# WiFi_Relays_Board_Kit.net
KiCad netlist of a schematic drawn in EAGLE
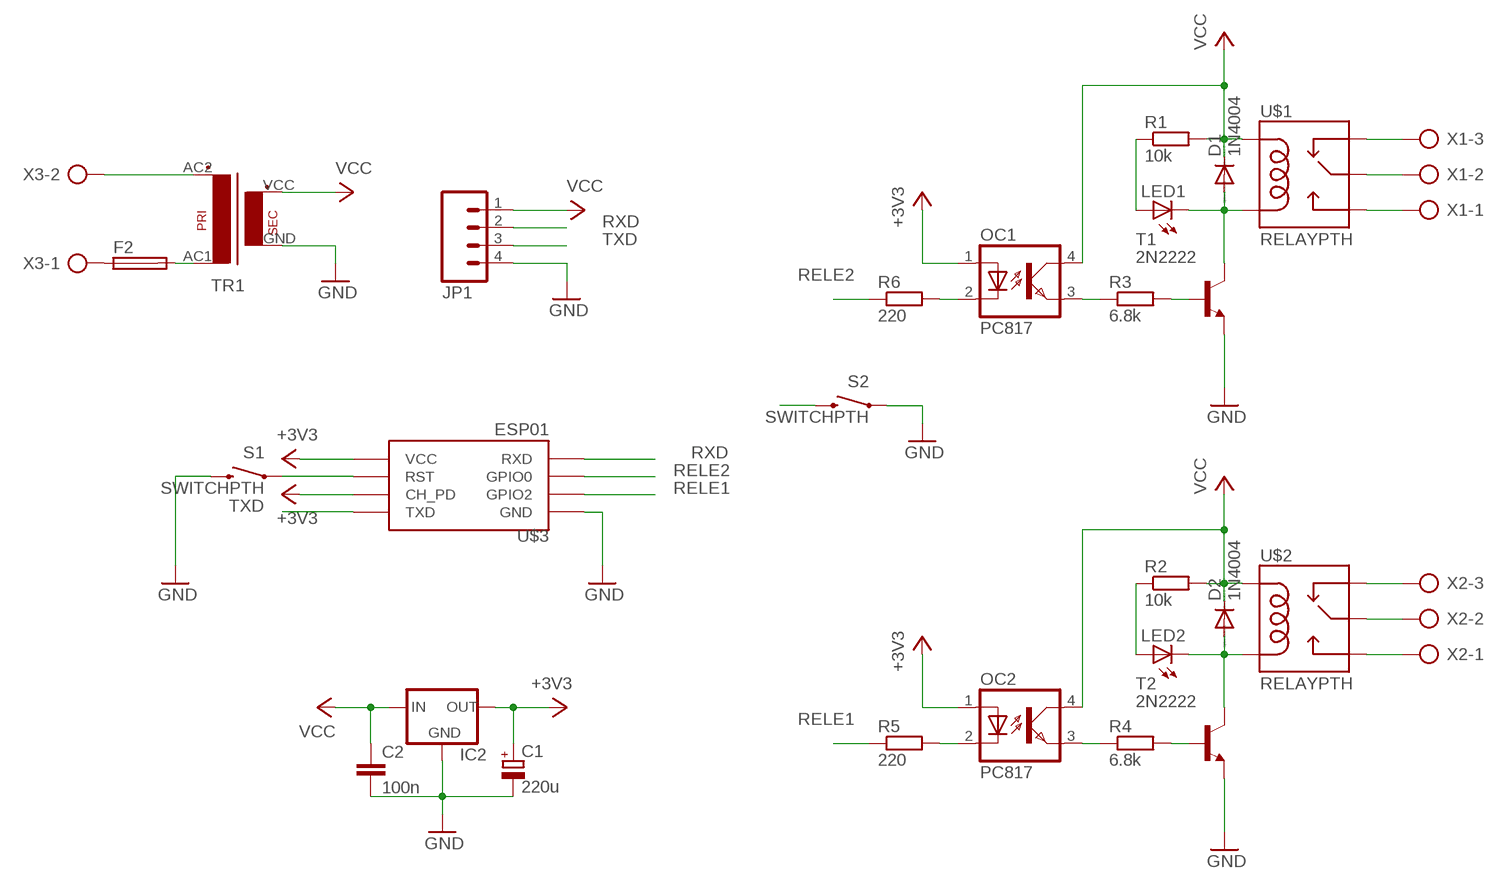
[diagram p0: schematic, sheet 1]

(export (version "E")
  (design (tool "Eeschema 10.0.6"))
  (components
    (comp (ref "C1")
      (value "220u")
      (footprint "eagle-import:E2,5-6")
      (libsource (lib "eagle-import") (part "CPOL-EUE2.5-6"))
    )
    (comp (ref "C2")
      (value "100n")
      (footprint "eagle-import:C050-024X044")
      (libsource (lib "eagle-import") (part "C-EU050-024X044"))
    )
    (comp (ref "D1")
      (value "1N4004")
      (footprint "eagle-import:DO41-10")
      (libsource (lib "eagle-import") (part "1N4004"))
    )
    (comp (ref "D2")
      (value "1N4004")
      (footprint "eagle-import:DO41-10")
      (libsource (lib "eagle-import") (part "1N4004"))
    )
    (comp (ref "F2")
      (value "SH22,5A")
      (footprint "eagle-import:SH22,5A")
      (fields (field (name "MPN") "0031.7701.11"))
      (libsource (lib "eagle-import") (part "SH22,5A"))
    )
    (comp (ref "IC2")
      (value "MCP1700TRI")
      (footprint "eagle-import:TO92")
      (libsource (lib "eagle-import") (part "MCP1700TRI"))
    )
    (comp (ref "JP1")
      (value "M04PTH")
      (footprint "eagle-import:1X04")
      (libsource (lib "eagle-import") (part "M04PTH"))
    )
    (comp (ref "LED1")
      (value "LED3MM")
      (footprint "eagle-import:LED3MM")
      (libsource (lib "eagle-import") (part "LED3MM"))
    )
    (comp (ref "LED2")
      (value "LED3MM")
      (footprint "eagle-import:LED3MM")
      (libsource (lib "eagle-import") (part "LED3MM"))
    )
    (comp (ref "OC1")
      (value "PC817")
      (footprint "eagle-import:DIL04")
      (fields (field (name "MPN") "PC817X4J000F"))
      (libsource (lib "eagle-import") (part "PC817"))
    )
    (comp (ref "OC2")
      (value "PC817")
      (footprint "eagle-import:DIL04")
      (fields (field (name "MPN") "PC817X4J000F"))
      (libsource (lib "eagle-import") (part "PC817"))
    )
    (comp (ref "R1")
      (value "10k")
      (footprint "eagle-import:0204_7")
      (libsource (lib "eagle-import") (part "resistor_R-EU_0204/7"))
    )
    (comp (ref "R2")
      (value "10k")
      (footprint "eagle-import:0204_7")
      (libsource (lib "eagle-import") (part "resistor_R-EU_0204/7"))
    )
    (comp (ref "R3")
      (value "6.8k")
      (footprint "eagle-import:0204_7")
      (libsource (lib "eagle-import") (part "R-EU_0204/7"))
    )
    (comp (ref "R4")
      (value "6.8k")
      (footprint "eagle-import:0204_7")
      (libsource (lib "eagle-import") (part "R-EU_0204/7"))
    )
    (comp (ref "R5")
      (value "220")
      (footprint "eagle-import:0204_7")
      (libsource (lib "eagle-import") (part "R-EU_0204/7"))
    )
    (comp (ref "R6")
      (value "220")
      (footprint "eagle-import:0204_7")
      (libsource (lib "eagle-import") (part "R-EU_0204/7"))
    )
    (comp (ref "S1")
      (value "SWITCHPTH")
      (footprint "eagle-import:TACTILE-PTH")
      (libsource (lib "eagle-import") (part "SWITCHPTH"))
    )
    (comp (ref "S2")
      (value "SWITCHPTH")
      (footprint "eagle-import:TACTILE-PTH")
      (libsource (lib "eagle-import") (part "SWITCHPTH"))
    )
    (comp (ref "T1")
      (value "2N2222")
      (footprint "eagle-import:TO92-EBC-OVAL")
      (libsource (lib "eagle-import") (part "2N2222"))
    )
    (comp (ref "T2")
      (value "2N2222")
      (footprint "eagle-import:TO92-EBC-OVAL")
      (libsource (lib "eagle-import") (part "2N2222"))
    )
    (comp (ref "TR1")
      (value "HLK-PM01")
      (footprint "eagle-import:HLK-PM01")
      (libsource (lib "eagle-import") (part "HLK-PM01"))
    )
    (comp (ref "U$1")
      (value "RELAYPTH")
      (footprint "eagle-import:SRD-05VDC-SL-C")
      (libsource (lib "eagle-import") (part "RELAYPTH"))
    )
    (comp (ref "U$2")
      (value "RELAYPTH")
      (footprint "eagle-import:SRD-05VDC-SL-C")
      (libsource (lib "eagle-import") (part "RELAYPTH"))
    )
    (comp (ref "U$3")
      (value "ESP01")
      (footprint "eagle-import:ESP01")
      (libsource (lib "eagle-import") (part "ESP01"))
    )
    (comp (ref "X1")
      (value "AK500/3")
      (footprint "eagle-import:AK500_3")
      (libsource (lib "eagle-import") (part "AK500/3"))
    )
    (comp (ref "X2")
      (value "AK500/3")
      (footprint "eagle-import:AK500_3")
      (libsource (lib "eagle-import") (part "AK500/3"))
    )
    (comp (ref "X3")
      (value "AK500/2")
      (footprint "eagle-import:AK500_2")
      (libsource (lib "eagle-import") (part "AK500/2"))
    )
  )
  (nets
    (net (code "1") (name "+3V3") (class "Default")
      (node (ref "C1") (pin "+") (pinfunction "+_+") (pintype "passive"))
      (node (ref "IC2") (pin "3") (pinfunction "OUT_3") (pintype "passive"))
      (node (ref "OC1") (pin "1") (pinfunction "A_1") (pintype "passive"))
      (node (ref "OC2") (pin "1") (pinfunction "A_1") (pintype "passive"))
      (node (ref "U$3") (pin "CH_PD") (pinfunction "CH_PD_CH_PD") (pintype "bidirectional"))
      (node (ref "U$3") (pin "VCC") (pinfunction "VCC_VCC") (pintype "bidirectional"))
    )
    (net (code "2") (name "/RELE1") (class "Default")
      (node (ref "R5") (pin "1") (pinfunction "1_1") (pintype "passive"))
      (node (ref "U$3") (pin "GPIO2") (pinfunction "GPIO2_GPIO2") (pintype "bidirectional"))
    )
    (net (code "3") (name "/RELE2") (class "Default")
      (node (ref "R6") (pin "1") (pinfunction "1_1") (pintype "passive"))
      (node (ref "S2") (pin "3") (pinfunction "2_3") (pintype "passive"))
      (node (ref "U$3") (pin "GPIO0") (pinfunction "GPIO0_GPIO0") (pintype "bidirectional"))
    )
    (net (code "4") (name "/RXD") (class "Default")
      (node (ref "JP1") (pin "2") (pinfunction "2_2") (pintype "passive"))
      (node (ref "U$3") (pin "RX") (pinfunction "RXD_RX") (pintype "bidirectional"))
    )
    (net (code "5") (name "/TXD") (class "Default")
      (node (ref "JP1") (pin "3") (pinfunction "3_3") (pintype "passive"))
      (node (ref "U$3") (pin "TX") (pinfunction "TXD_TX") (pintype "bidirectional"))
    )
    (net (code "6") (name "GND") (class "Default")
      (node (ref "C1") (pin "-") (pinfunction "-_-") (pintype "passive"))
      (node (ref "C2") (pin "2") (pinfunction "2_2") (pintype "passive"))
      (node (ref "IC2") (pin "1") (pinfunction "GND_1") (pintype "input"))
      (node (ref "JP1") (pin "4") (pinfunction "4_4") (pintype "passive"))
      (node (ref "S1") (pin "3") (pinfunction "2_3") (pintype "passive"))
      (node (ref "S2") (pin "1") (pinfunction "1_1") (pintype "passive"))
      (node (ref "T1") (pin "E") (pinfunction "E_E") (pintype "passive"))
      (node (ref "T2") (pin "E") (pinfunction "E_E") (pintype "passive"))
      (node (ref "TR1") (pin "GND") (pinfunction "S4_GND") (pintype "passive"))
      (node (ref "U$3") (pin "GND") (pinfunction "GND_GND") (pintype "bidirectional"))
    )
    (net (code "7") (name "Net-(LED1-C)") (class "Default")
      (node (ref "D1") (pin "A") (pinfunction "A_A") (pintype "passive"))
      (node (ref "LED1") (pin "K") (pinfunction "C_K") (pintype "passive"))
      (node (ref "T1") (pin "C") (pinfunction "C_C") (pintype "passive"))
      (node (ref "U$1") (pin "COIL0") (pinfunction "COIL0_COIL0") (pintype "bidirectional"))
    )
    (net (code "8") (name "Net-(LED1-PadA)") (class "Default")
      (node (ref "LED1") (pin "A") (pinfunction "A_A") (pintype "passive"))
      (node (ref "R1") (pin "1") (pinfunction "1_1") (pintype "passive"))
    )
    (net (code "9") (name "Net-(LED2-C)") (class "Default")
      (node (ref "D2") (pin "A") (pinfunction "A_A") (pintype "passive"))
      (node (ref "LED2") (pin "K") (pinfunction "C_K") (pintype "passive"))
      (node (ref "T2") (pin "C") (pinfunction "C_C") (pintype "passive"))
      (node (ref "U$2") (pin "COIL0") (pinfunction "COIL0_COIL0") (pintype "bidirectional"))
    )
    (net (code "10") (name "Net-(LED2-PadA)") (class "Default")
      (node (ref "LED2") (pin "A") (pinfunction "A_A") (pintype "passive"))
      (node (ref "R2") (pin "1") (pinfunction "1_1") (pintype "passive"))
    )
    (net (code "11") (name "Net-(OC1-C)") (class "Default")
      (node (ref "OC1") (pin "2") (pinfunction "C_2") (pintype "passive"))
      (node (ref "R6") (pin "2") (pinfunction "2_2") (pintype "passive"))
    )
    (net (code "12") (name "Net-(OC1-EMIT)") (class "Default")
      (node (ref "OC1") (pin "3") (pinfunction "EMIT_3") (pintype "passive"))
      (node (ref "R3") (pin "1") (pinfunction "1_1") (pintype "passive"))
    )
    (net (code "13") (name "Net-(OC2-C)") (class "Default")
      (node (ref "OC2") (pin "2") (pinfunction "C_2") (pintype "passive"))
      (node (ref "R5") (pin "2") (pinfunction "2_2") (pintype "passive"))
    )
    (net (code "14") (name "Net-(OC2-EMIT)") (class "Default")
      (node (ref "OC2") (pin "3") (pinfunction "EMIT_3") (pintype "passive"))
      (node (ref "R4") (pin "1") (pinfunction "1_1") (pintype "passive"))
    )
    (net (code "15") (name "Net-(R3-Pad2)") (class "Default")
      (node (ref "R3") (pin "2") (pinfunction "2_2") (pintype "passive"))
      (node (ref "T1") (pin "B") (pinfunction "B_B") (pintype "passive"))
    )
    (net (code "16") (name "Net-(R4-Pad2)") (class "Default")
      (node (ref "R4") (pin "2") (pinfunction "2_2") (pintype "passive"))
      (node (ref "T2") (pin "B") (pinfunction "B_B") (pintype "passive"))
    )
    (net (code "17") (name "Net-(S1-Pad1)") (class "Default")
      (node (ref "S1") (pin "1") (pinfunction "1_1") (pintype "passive"))
      (node (ref "U$3") (pin "RST") (pinfunction "RST_RST") (pintype "bidirectional"))
    )
    (net (code "18") (name "Net-(TR1-P1)") (class "Default")
      (node (ref "F2") (pin "2") (pinfunction "2_2") (pintype "passive"))
      (node (ref "TR1") (pin "AC1") (pinfunction "P1_AC1") (pintype "passive"))
    )
    (net (code "19") (name "Net-(TR1-P2)") (class "Default")
      (node (ref "TR1") (pin "AC2") (pinfunction "P2_AC2") (pintype "passive"))
      (node (ref "X3") (pin "2") (pinfunction "KL_2") (pintype "passive"))
    )
    (net (code "20") (name "Net-(U$1-SWCLOSE)") (class "Default")
      (node (ref "U$1") (pin "SWCLOSED") (pinfunction "SWCLOSE_SWCLOSED") (pintype "bidirectional"))
      (node (ref "X1") (pin "3") (pinfunction "KL_3") (pintype "passive"))
    )
    (net (code "21") (name "Net-(U$2-SWCLOSE)") (class "Default")
      (node (ref "U$2") (pin "SWCLOSED") (pinfunction "SWCLOSE_SWCLOSED") (pintype "bidirectional"))
      (node (ref "X2") (pin "3") (pinfunction "KL_3") (pintype "passive"))
    )
    (net (code "22") (name "Net-(X1A-KL)") (class "Default")
      (node (ref "U$1") (pin "SWOPEN") (pinfunction "SWOPEN_SWOPEN") (pintype "bidirectional"))
      (node (ref "X1") (pin "1") (pinfunction "KL_1") (pintype "passive"))
    )
    (net (code "23") (name "Net-(X1B-KL)") (class "Default")
      (node (ref "U$1") (pin "SWCOMMON") (pinfunction "SWCOMMON_SWCOMMON") (pintype "bidirectional"))
      (node (ref "X1") (pin "2") (pinfunction "KL_2") (pintype "passive"))
    )
    (net (code "24") (name "Net-(X2A-KL)") (class "Default")
      (node (ref "U$2") (pin "SWOPEN") (pinfunction "SWOPEN_SWOPEN") (pintype "bidirectional"))
      (node (ref "X2") (pin "1") (pinfunction "KL_1") (pintype "passive"))
    )
    (net (code "25") (name "Net-(X2B-KL)") (class "Default")
      (node (ref "U$2") (pin "SWCOMMON") (pinfunction "SWCOMMON_SWCOMMON") (pintype "bidirectional"))
      (node (ref "X2") (pin "2") (pinfunction "KL_2") (pintype "passive"))
    )
    (net (code "26") (name "Net-(X3A-KL)") (class "Default")
      (node (ref "F2") (pin "1") (pinfunction "1_1") (pintype "passive"))
      (node (ref "X3") (pin "1") (pinfunction "KL_1") (pintype "passive"))
    )
    (net (code "27") (name "VCC") (class "Default")
      (node (ref "C2") (pin "1") (pinfunction "1_1") (pintype "passive"))
      (node (ref "D1") (pin "C") (pinfunction "C_C") (pintype "passive"))
      (node (ref "D2") (pin "C") (pinfunction "C_C") (pintype "passive"))
      (node (ref "IC2") (pin "2") (pinfunction "IN_2") (pintype "input"))
      (node (ref "JP1") (pin "1") (pinfunction "1_1") (pintype "passive"))
      (node (ref "OC1") (pin "4") (pinfunction "COL_4") (pintype "passive"))
      (node (ref "OC2") (pin "4") (pinfunction "COL_4") (pintype "passive"))
      (node (ref "R1") (pin "2") (pinfunction "2_2") (pintype "passive"))
      (node (ref "R2") (pin "2") (pinfunction "2_2") (pintype "passive"))
      (node (ref "TR1") (pin "VCC") (pinfunction "S3_VCC") (pintype "passive"))
      (node (ref "U$1") (pin "COIL1") (pinfunction "COIL1_COIL1") (pintype "bidirectional"))
      (node (ref "U$2") (pin "COIL1") (pinfunction "COIL1_COIL1") (pintype "bidirectional"))
    )
  )
)
